# PandaSat_Payload.net
KiCad netlist of a schematic drawn in EAGLE
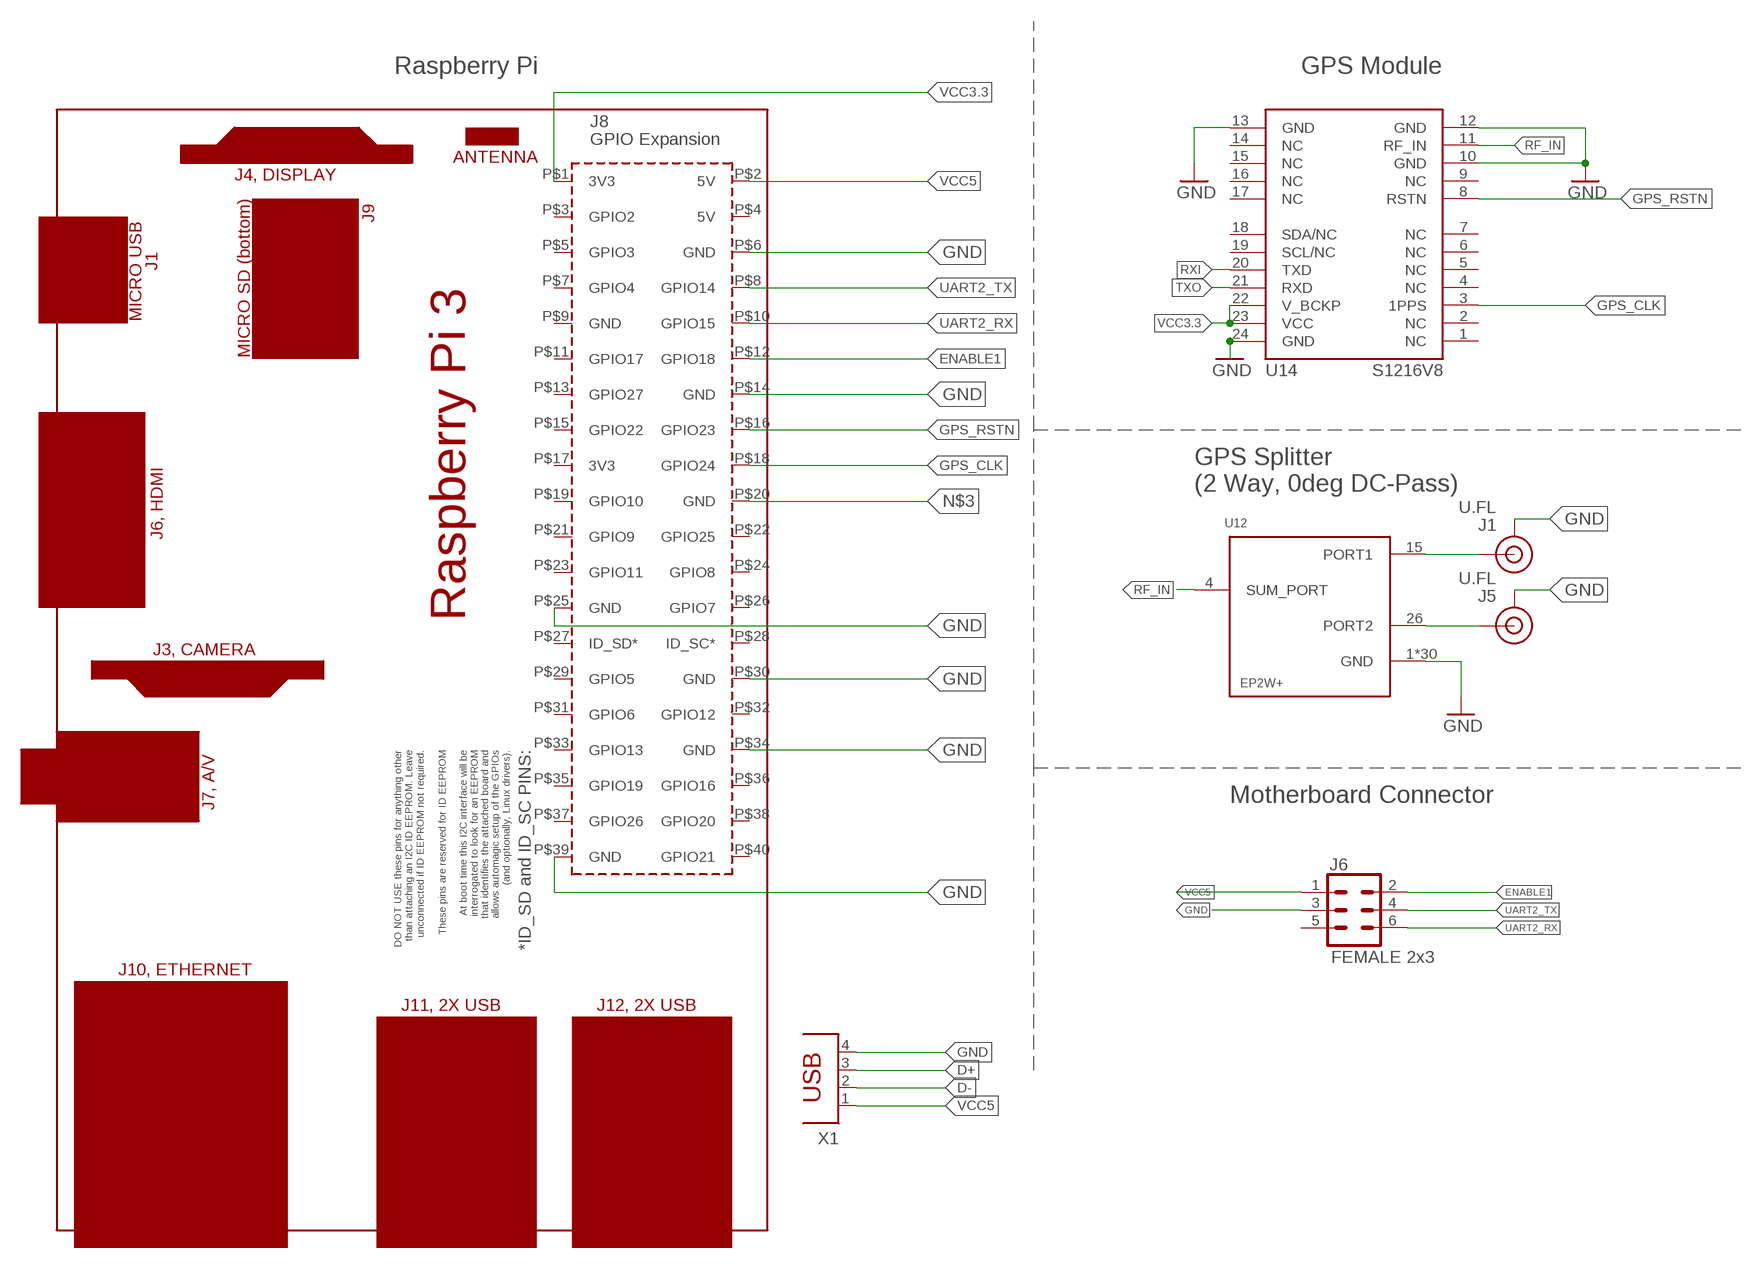
[diagram p0: schematic, sheet 1]
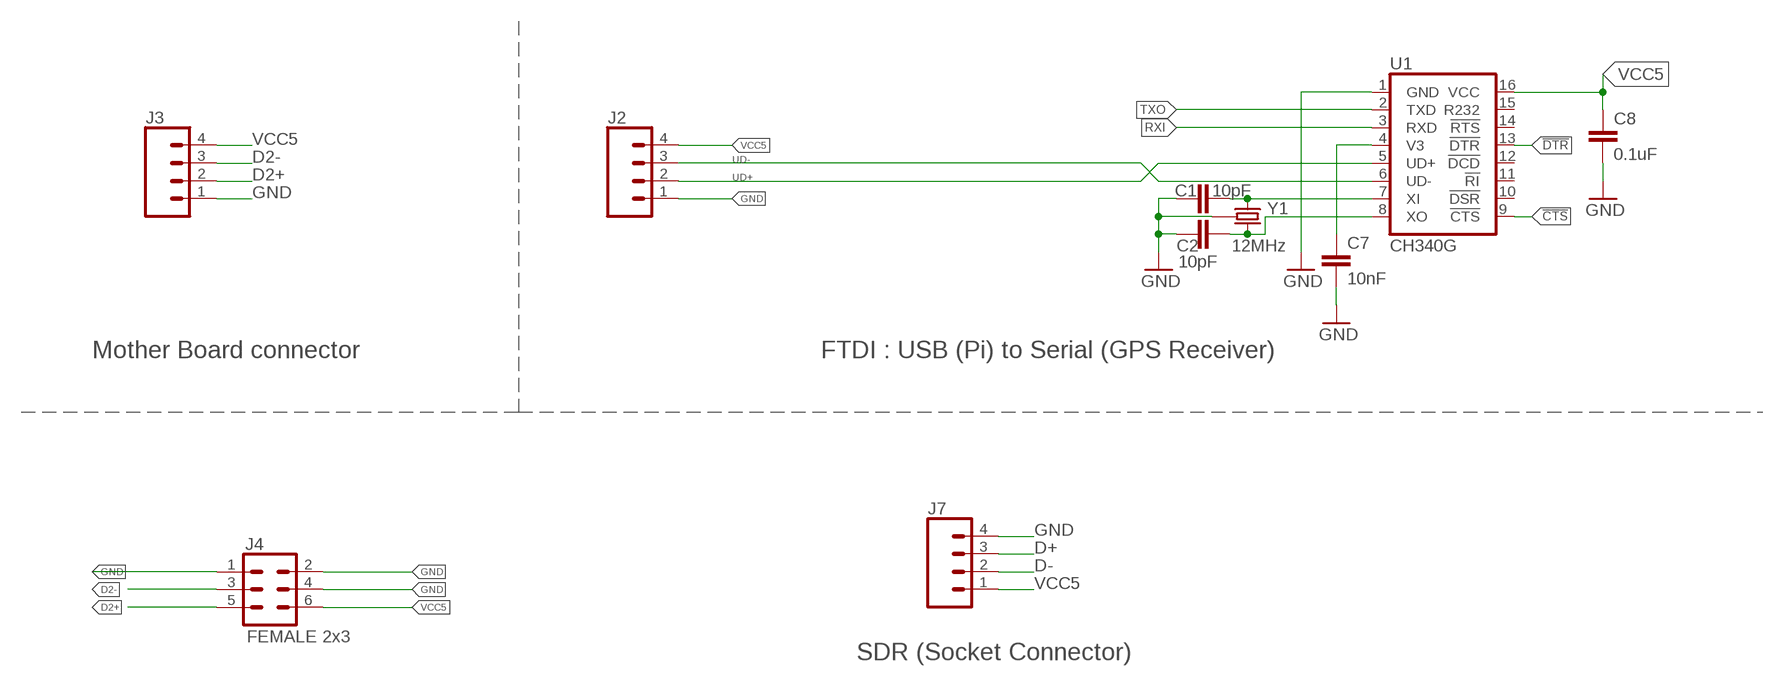
[diagram p1: schematic, sheet 2]

(export (version "E")
  (design (tool "Eeschema 10.0.6"))
  (components
    (comp (ref "C1")
      (value "10pF")
      (footprint "eagle-import:0603-CAP")
      (libsource (lib "eagle-import") (part "10PF-50V-5%(0603)"))
    )
    (comp (ref "C2")
      (value "10pF")
      (footprint "eagle-import:0603-CAP")
      (libsource (lib "eagle-import") (part "10PF-50V-5%(0603)"))
    )
    (comp (ref "C7")
      (value "10nF")
      (footprint "eagle-import:0603-CAP")
      (libsource (lib "eagle-import") (part "10NF/10000PF-50V-10%(0603)"))
    )
    (comp (ref "C8")
      (value "0.1uF")
      (footprint "eagle-import:0603-CAP")
      (libsource (lib "eagle-import") (part "0.1UF-25V(+80/-20%)(0603)"))
    )
    (comp (ref "J2")
      (value "CONN_04")
      (footprint "eagle-import:1X04")
      (libsource (lib "eagle-import") (part "CONN_04"))
    )
    (comp (ref "J3")
      (value "CONN_04")
      (footprint "eagle-import:1X04")
      (libsource (lib "eagle-import") (part "CONN_04"))
    )
    (comp (ref "J4")
      (value "FEMALE 2x3")
      (footprint "eagle-import:2X3")
      (libsource (lib "eagle-import") (part "CONN_03X2FEMALE"))
    )
    (comp (ref "J7")
      (value "CONN_04")
      (footprint "eagle-import:1X04")
      (libsource (lib "eagle-import") (part "CONN_04"))
    )
    (comp (ref "U1")
      (value "CH340G")
      (footprint "eagle-import:SO016")
      (libsource (lib "eagle-import") (part "CH340GSMD"))
    )
    (comp (ref "Y1")
      (value "12MHz")
      (footprint "eagle-import:CRYSTAL-SMD-3.2X2.5")
      (libsource (lib "eagle-import") (part "CRYSTAL-GROUNDED3.2X2.5"))
    )
    (comp (ref "J1")
      (value "U.FL")
      (footprint "eagle-import:U.FL")
      (libsource (lib "eagle-import") (part "U.FL2PIN"))
    )
    (comp (ref "J5")
      (value "U.FL")
      (footprint "eagle-import:U.FL")
      (libsource (lib "eagle-import") (part "U.FL2PIN"))
    )
    (comp (ref "J6")
      (value "FEMALE 2x3")
      (footprint "eagle-import:2X3")
      (libsource (lib "eagle-import") (part "CONN_03X2FEMALE"))
    )
    (comp (ref "PCB1")
      (value "RPI3RPI3")
      (footprint "eagle-import:RPI3")
      (libsource (lib "eagle-import") (part "RPI3RPI3"))
    )
    (comp (ref "U12")
      (value "EP2W+")
      (footprint "eagle-import:QFN32-5X5MM")
      (libsource (lib "eagle-import") (part "EP2W+"))
    )
    (comp (ref "U14")
      (value "S1216V8")
      (footprint "eagle-import:S1216_24PIN_PACKAGE")
      (libsource (lib "eagle-import") (part "S1216V8"))
    )
    (comp (ref "X1")
      (value "PN87520")
      (footprint "eagle-import:PN87520")
      (libsource (lib "eagle-import") (part "PN87520"))
    )
  )
  (nets
    (net (code "1") (name "D+") (class "Default")
      (node (ref "J7") (pin "3") (pinfunction "3_3") (pintype "passive"))
      (node (ref "X1") (pin "3") (pinfunction "3_3") (pintype "passive"))
    )
    (net (code "2") (name "D-") (class "Default")
      (node (ref "J7") (pin "2") (pinfunction "2_2") (pintype "passive"))
      (node (ref "X1") (pin "2") (pinfunction "2_2") (pintype "passive"))
    )
    (net (code "3") (name "D2+") (class "Default")
      (node (ref "J3") (pin "2") (pinfunction "2_2") (pintype "passive"))
      (node (ref "J4") (pin "5") (pinfunction "5_5") (pintype "bidirectional"))
    )
    (net (code "4") (name "D2-") (class "Default")
      (node (ref "J3") (pin "3") (pinfunction "3_3") (pintype "passive"))
      (node (ref "J4") (pin "3") (pinfunction "3_3") (pintype "bidirectional"))
    )
    (net (code "5") (name "ENABLE1") (class "Default")
      (node (ref "J6") (pin "2") (pinfunction "2_2") (pintype "bidirectional"))
      (node (ref "PCB1") (pin "P$12") (pinfunction "GPIO18_P$12") (pintype "bidirectional"))
    )
    (net (code "6") (name "GND") (class "Default")
      (node (ref "C1") (pin "1") (pinfunction "1_1") (pintype "passive"))
      (node (ref "C2") (pin "1") (pinfunction "1_1") (pintype "passive"))
      (node (ref "C7") (pin "2") (pinfunction "2_2") (pintype "passive"))
      (node (ref "C8") (pin "2") (pinfunction "2_2") (pintype "passive"))
      (node (ref "J1") (pin "1") (pinfunction "GND_1") (pintype "bidirectional"))
      (node (ref "J1") (pin "2") (pinfunction "GND_2") (pintype "bidirectional"))
      (node (ref "J2") (pin "1") (pinfunction "1_1") (pintype "passive"))
      (node (ref "J3") (pin "1") (pinfunction "1_1") (pintype "passive"))
      (node (ref "J4") (pin "1") (pinfunction "1_1") (pintype "bidirectional"))
      (node (ref "J4") (pin "2") (pinfunction "2_2") (pintype "bidirectional"))
      (node (ref "J4") (pin "4") (pinfunction "4_4") (pintype "bidirectional"))
      (node (ref "J5") (pin "1") (pinfunction "GND_1") (pintype "bidirectional"))
      (node (ref "J5") (pin "2") (pinfunction "GND_2") (pintype "bidirectional"))
      (node (ref "J6") (pin "3") (pinfunction "3_3") (pintype "bidirectional"))
      (node (ref "J7") (pin "4") (pinfunction "4_4") (pintype "passive"))
      (node (ref "PCB1") (pin "P$14") (pinfunction "GND_P$14") (pintype "bidirectional"))
      (node (ref "PCB1") (pin "P$25") (pinfunction "GND_P$25") (pintype "bidirectional"))
      (node (ref "PCB1") (pin "P$30") (pinfunction "GND_P$30") (pintype "bidirectional"))
      (node (ref "PCB1") (pin "P$34") (pinfunction "GND_P$34") (pintype "bidirectional"))
      (node (ref "PCB1") (pin "P$39") (pinfunction "GND_P$39") (pintype "bidirectional"))
      (node (ref "PCB1") (pin "P$6") (pinfunction "GND_P$6") (pintype "bidirectional"))
      (node (ref "U1") (pin "1") (pinfunction "GND_1") (pintype "bidirectional"))
      (node (ref "U12") (pin "1") (pinfunction "GND_1") (pintype "bidirectional"))
      (node (ref "U12") (pin "10") (pinfunction "GND_10") (pintype "bidirectional"))
      (node (ref "U12") (pin "11") (pinfunction "GND_11") (pintype "bidirectional"))
      (node (ref "U12") (pin "12") (pinfunction "GND_12") (pintype "bidirectional"))
      (node (ref "U12") (pin "13") (pinfunction "GND_13") (pintype "bidirectional"))
      (node (ref "U12") (pin "14") (pinfunction "GND_14") (pintype "bidirectional"))
      (node (ref "U12") (pin "16") (pinfunction "GND_16") (pintype "bidirectional"))
      (node (ref "U12") (pin "17") (pinfunction "GND_17") (pintype "bidirectional"))
      (node (ref "U12") (pin "18") (pinfunction "GND_18") (pintype "bidirectional"))
      (node (ref "U12") (pin "19") (pinfunction "GND_19") (pintype "bidirectional"))
      (node (ref "U12") (pin "2") (pinfunction "GND_2") (pintype "bidirectional"))
      (node (ref "U12") (pin "20") (pinfunction "GND_20") (pintype "bidirectional"))
      (node (ref "U12") (pin "21") (pinfunction "GND_21") (pintype "bidirectional"))
      (node (ref "U12") (pin "22") (pinfunction "GND_22") (pintype "bidirectional"))
      (node (ref "U12") (pin "23") (pinfunction "GND_23") (pintype "bidirectional"))
      (node (ref "U12") (pin "24") (pinfunction "GND_24") (pintype "bidirectional"))
      (node (ref "U12") (pin "25") (pinfunction "GND_25") (pintype "bidirectional"))
      (node (ref "U12") (pin "27") (pinfunction "GND_27") (pintype "bidirectional"))
      (node (ref "U12") (pin "28") (pinfunction "GND_28") (pintype "bidirectional"))
      (node (ref "U12") (pin "29") (pinfunction "GND_29") (pintype "bidirectional"))
      (node (ref "U12") (pin "3") (pinfunction "GND_3") (pintype "bidirectional"))
      (node (ref "U12") (pin "30") (pinfunction "GND_30") (pintype "bidirectional"))
      (node (ref "U12") (pin "31") (pinfunction "GND_31") (pintype "bidirectional"))
      (node (ref "U12") (pin "32") (pinfunction "GND_32") (pintype "bidirectional"))
      (node (ref "U12") (pin "5") (pinfunction "GND_5") (pintype "bidirectional"))
      (node (ref "U12") (pin "6") (pinfunction "GND_6") (pintype "bidirectional"))
      (node (ref "U12") (pin "7") (pinfunction "GND_7") (pintype "bidirectional"))
      (node (ref "U12") (pin "8") (pinfunction "GND_8") (pintype "bidirectional"))
      (node (ref "U12") (pin "9") (pinfunction "GND_9") (pintype "bidirectional"))
      (node (ref "U12") (pin "EP") (pinfunction "GND_EP") (pintype "bidirectional"))
      (node (ref "U14") (pin "10") (pinfunction "GND_10") (pintype "bidirectional"))
      (node (ref "U14") (pin "12") (pinfunction "GND_12") (pintype "bidirectional"))
      (node (ref "U14") (pin "13") (pinfunction "GND_13") (pintype "bidirectional"))
      (node (ref "U14") (pin "24") (pinfunction "GND_24") (pintype "bidirectional"))
      (node (ref "X1") (pin "4") (pinfunction "4_4") (pintype "passive"))
      (node (ref "Y1") (pin "2") (pinfunction "GND_2") (pintype "passive"))
      (node (ref "Y1") (pin "4") (pinfunction "GND_4") (pintype "passive"))
    )
    (net (code "7") (name "GPS_CLK") (class "Default")
      (node (ref "PCB1") (pin "P$18") (pinfunction "GPIO24_P$18") (pintype "bidirectional"))
      (node (ref "U14") (pin "3") (pinfunction "1PPS_3") (pintype "bidirectional"))
    )
    (net (code "8") (name "GPS_RSTN") (class "Default")
      (node (ref "PCB1") (pin "P$16") (pinfunction "GPIO23_P$16") (pintype "bidirectional"))
      (node (ref "U14") (pin "8") (pinfunction "RSTN_8") (pintype "bidirectional"))
    )
    (net (code "9") (name "N$3") (class "Default")
      (node (ref "PCB1") (pin "P$20") (pinfunction "GND_P$20") (pintype "bidirectional"))
    )
    (net (code "10") (name "Net-(J1-SIGNAL)") (class "Default")
      (node (ref "J1") (pin "FEED") (pinfunction "SIGNAL_FEED") (pintype "bidirectional"))
      (node (ref "U12") (pin "15") (pinfunction "PORT1_15") (pintype "bidirectional"))
    )
    (net (code "11") (name "Net-(J5-SIGNAL)") (class "Default")
      (node (ref "J5") (pin "FEED") (pinfunction "SIGNAL_FEED") (pintype "bidirectional"))
      (node (ref "U12") (pin "26") (pinfunction "PORT2_26") (pintype "bidirectional"))
    )
    (net (code "12") (name "Net-(U1-V3)") (class "Default")
      (node (ref "C7") (pin "1") (pinfunction "1_1") (pintype "passive"))
      (node (ref "U1") (pin "4") (pinfunction "V3_4") (pintype "bidirectional"))
    )
    (net (code "13") (name "Net-(U1-XI)") (class "Default")
      (node (ref "C1") (pin "2") (pinfunction "2_2") (pintype "passive"))
      (node (ref "U1") (pin "7") (pinfunction "XI_7") (pintype "bidirectional"))
      (node (ref "Y1") (pin "1") (pinfunction "1_1") (pintype "passive"))
    )
    (net (code "14") (name "Net-(U1-XO)") (class "Default")
      (node (ref "C2") (pin "2") (pinfunction "2_2") (pintype "passive"))
      (node (ref "U1") (pin "8") (pinfunction "XO_8") (pintype "bidirectional"))
      (node (ref "Y1") (pin "3") (pinfunction "2_3") (pintype "passive"))
    )
    (net (code "15") (name "RF_IN") (class "Default")
      (node (ref "U12") (pin "4") (pinfunction "SUM_PORT_4") (pintype "bidirectional"))
      (node (ref "U14") (pin "11") (pinfunction "RF_IN_11") (pintype "bidirectional"))
    )
    (net (code "16") (name "RXI") (class "Default")
      (node (ref "U1") (pin "3") (pinfunction "RXD_3") (pintype "bidirectional"))
      (node (ref "U14") (pin "20") (pinfunction "TXD_20") (pintype "bidirectional"))
    )
    (net (code "17") (name "TXO") (class "Default")
      (node (ref "U1") (pin "2") (pinfunction "TXD_2") (pintype "bidirectional"))
      (node (ref "U14") (pin "21") (pinfunction "RXD_21") (pintype "bidirectional"))
    )
    (net (code "18") (name "UART2_RX") (class "Default")
      (node (ref "J6") (pin "6") (pinfunction "6_6") (pintype "bidirectional"))
      (node (ref "PCB1") (pin "P$10") (pinfunction "GPIO15_P$10") (pintype "bidirectional"))
    )
    (net (code "19") (name "UART2_TX") (class "Default")
      (node (ref "J6") (pin "4") (pinfunction "4_4") (pintype "bidirectional"))
      (node (ref "PCB1") (pin "P$8") (pinfunction "GPIO14_P$8") (pintype "bidirectional"))
    )
    (net (code "20") (name "UD+") (class "Default")
      (node (ref "J2") (pin "2") (pinfunction "2_2") (pintype "passive"))
      (node (ref "U1") (pin "5") (pinfunction "UD+_5") (pintype "bidirectional"))
    )
    (net (code "21") (name "UD-") (class "Default")
      (node (ref "J2") (pin "3") (pinfunction "3_3") (pintype "passive"))
      (node (ref "U1") (pin "6") (pinfunction "UD-_6") (pintype "bidirectional"))
    )
    (net (code "22") (name "VCC3.3") (class "Default")
      (node (ref "PCB1") (pin "P$1") (pinfunction "3V3_P$1") (pintype "bidirectional"))
      (node (ref "U14") (pin "22") (pinfunction "V_BCKP_22") (pintype "bidirectional"))
      (node (ref "U14") (pin "23") (pinfunction "VCC_23") (pintype "bidirectional"))
    )
    (net (code "23") (name "VCC5") (class "Default")
      (node (ref "C8") (pin "1") (pinfunction "1_1") (pintype "passive"))
      (node (ref "J2") (pin "4") (pinfunction "4_4") (pintype "passive"))
      (node (ref "J3") (pin "4") (pinfunction "4_4") (pintype "passive"))
      (node (ref "J4") (pin "6") (pinfunction "6_6") (pintype "bidirectional"))
      (node (ref "J6") (pin "1") (pinfunction "1_1") (pintype "bidirectional"))
      (node (ref "J7") (pin "1") (pinfunction "1_1") (pintype "passive"))
      (node (ref "PCB1") (pin "P$2") (pinfunction "5V_P$2") (pintype "bidirectional"))
      (node (ref "U1") (pin "16") (pinfunction "VCC_16") (pintype "bidirectional"))
      (node (ref "X1") (pin "1") (pinfunction "1_1") (pintype "passive"))
    )
    (net (code "24") (name "unconnected-(J6-Pad5)") (class "Default")
      (node (ref "J6") (pin "5") (pinfunction "5_5") (pintype "bidirectional"))
    )
    (net (code "25") (name "unconnected-(PCB1-3V3-PadP$17)") (class "Default")
      (node (ref "PCB1") (pin "P$17") (pinfunction "3V3_P$17") (pintype "bidirectional"))
    )
    (net (code "26") (name "unconnected-(PCB1-5V-PadP$4)") (class "Default")
      (node (ref "PCB1") (pin "P$4") (pinfunction "5V_P$4") (pintype "bidirectional"))
    )
    (net (code "27") (name "unconnected-(PCB1-GND-PadP$9)") (class "Default")
      (node (ref "PCB1") (pin "P$9") (pinfunction "GND_P$9") (pintype "bidirectional"))
    )
    (net (code "28") (name "unconnected-(PCB1-GPIO2-PadP$3)") (class "Default")
      (node (ref "PCB1") (pin "P$3") (pinfunction "GPIO2_P$3") (pintype "bidirectional"))
    )
    (net (code "29") (name "unconnected-(PCB1-GPIO3-PadP$5)") (class "Default")
      (node (ref "PCB1") (pin "P$5") (pinfunction "GPIO3_P$5") (pintype "bidirectional"))
    )
    (net (code "30") (name "unconnected-(PCB1-GPIO4-PadP$7)") (class "Default")
      (node (ref "PCB1") (pin "P$7") (pinfunction "GPIO4_P$7") (pintype "bidirectional"))
    )
    (net (code "31") (name "unconnected-(PCB1-GPIO5-PadP$29)") (class "Default")
      (node (ref "PCB1") (pin "P$29") (pinfunction "GPIO5_P$29") (pintype "bidirectional"))
    )
    (net (code "32") (name "unconnected-(PCB1-GPIO6-PadP$31)") (class "Default")
      (node (ref "PCB1") (pin "P$31") (pinfunction "GPIO6_P$31") (pintype "bidirectional"))
    )
    (net (code "33") (name "unconnected-(PCB1-GPIO7-PadP$26)") (class "Default")
      (node (ref "PCB1") (pin "P$26") (pinfunction "GPIO7_P$26") (pintype "bidirectional"))
    )
    (net (code "34") (name "unconnected-(PCB1-GPIO8-PadP$24)") (class "Default")
      (node (ref "PCB1") (pin "P$24") (pinfunction "GPIO8_P$24") (pintype "bidirectional"))
    )
    (net (code "35") (name "unconnected-(PCB1-GPIO9-PadP$21)") (class "Default")
      (node (ref "PCB1") (pin "P$21") (pinfunction "GPIO9_P$21") (pintype "bidirectional"))
    )
    (net (code "36") (name "unconnected-(PCB1-GPIO10-PadP$19)") (class "Default")
      (node (ref "PCB1") (pin "P$19") (pinfunction "GPIO10_P$19") (pintype "bidirectional"))
    )
    (net (code "37") (name "unconnected-(PCB1-GPIO11-PadP$23)") (class "Default")
      (node (ref "PCB1") (pin "P$23") (pinfunction "GPIO11_P$23") (pintype "bidirectional"))
    )
    (net (code "38") (name "unconnected-(PCB1-GPIO12-PadP$32)") (class "Default")
      (node (ref "PCB1") (pin "P$32") (pinfunction "GPIO12_P$32") (pintype "bidirectional"))
    )
    (net (code "39") (name "unconnected-(PCB1-GPIO13-PadP$33)") (class "Default")
      (node (ref "PCB1") (pin "P$33") (pinfunction "GPIO13_P$33") (pintype "bidirectional"))
    )
    (net (code "40") (name "unconnected-(PCB1-GPIO16-PadP$36)") (class "Default")
      (node (ref "PCB1") (pin "P$36") (pinfunction "GPIO16_P$36") (pintype "bidirectional"))
    )
    (net (code "41") (name "unconnected-(PCB1-GPIO17-PadP$11)") (class "Default")
      (node (ref "PCB1") (pin "P$11") (pinfunction "GPIO17_P$11") (pintype "bidirectional"))
    )
    (net (code "42") (name "unconnected-(PCB1-GPIO19-PadP$35)") (class "Default")
      (node (ref "PCB1") (pin "P$35") (pinfunction "GPIO19_P$35") (pintype "bidirectional"))
    )
    (net (code "43") (name "unconnected-(PCB1-GPIO20-PadP$38)") (class "Default")
      (node (ref "PCB1") (pin "P$38") (pinfunction "GPIO20_P$38") (pintype "bidirectional"))
    )
    (net (code "44") (name "unconnected-(PCB1-GPIO21-PadP$40)") (class "Default")
      (node (ref "PCB1") (pin "P$40") (pinfunction "GPIO21_P$40") (pintype "bidirectional"))
    )
    (net (code "45") (name "unconnected-(PCB1-GPIO22-PadP$15)") (class "Default")
      (node (ref "PCB1") (pin "P$15") (pinfunction "GPIO22_P$15") (pintype "bidirectional"))
    )
    (net (code "46") (name "unconnected-(PCB1-GPIO25-PadP$22)") (class "Default")
      (node (ref "PCB1") (pin "P$22") (pinfunction "GPIO25_P$22") (pintype "bidirectional"))
    )
    (net (code "47") (name "unconnected-(PCB1-GPIO26-PadP$37)") (class "Default")
      (node (ref "PCB1") (pin "P$37") (pinfunction "GPIO26_P$37") (pintype "bidirectional"))
    )
    (net (code "48") (name "unconnected-(PCB1-GPIO27-PadP$13)") (class "Default")
      (node (ref "PCB1") (pin "P$13") (pinfunction "GPIO27_P$13") (pintype "bidirectional"))
    )
    (net (code "49") (name "unconnected-(PCB1-ID_SC*-PadP$28)") (class "Default")
      (node (ref "PCB1") (pin "P$28") (pinfunction "ID_SC*_P$28") (pintype "bidirectional"))
    )
    (net (code "50") (name "unconnected-(PCB1-ID_SD*-PadP$27)") (class "Default")
      (node (ref "PCB1") (pin "P$27") (pinfunction "ID_SD*_P$27") (pintype "bidirectional"))
    )
    (net (code "51") (name "unconnected-(U1-R232-Pad15)") (class "Default")
      (node (ref "U1") (pin "15") (pinfunction "R232_15") (pintype "bidirectional"))
    )
    (net (code "52") (name "unconnected-(U1-~{DCD}-Pad12)") (class "Default")
      (node (ref "U1") (pin "12") (pinfunction "~{DCD}_12") (pintype "bidirectional"))
    )
    (net (code "53") (name "unconnected-(U1-~{DSR}-Pad10)") (class "Default")
      (node (ref "U1") (pin "10") (pinfunction "~{DSR}_10") (pintype "bidirectional"))
    )
    (net (code "54") (name "unconnected-(U1-~{RI}-Pad11)") (class "Default")
      (node (ref "U1") (pin "11") (pinfunction "~{RI}_11") (pintype "bidirectional"))
    )
    (net (code "55") (name "unconnected-(U1-~{RTS}-Pad14)") (class "Default")
      (node (ref "U1") (pin "14") (pinfunction "~{RTS}_14") (pintype "bidirectional"))
    )
    (net (code "56") (name "unconnected-(U14-NC-Pad1)") (class "Default")
      (node (ref "U14") (pin "1") (pinfunction "NC_1") (pintype "bidirectional"))
    )
    (net (code "57") (name "unconnected-(U14-NC-Pad2)") (class "Default")
      (node (ref "U14") (pin "2") (pinfunction "NC_2") (pintype "bidirectional"))
    )
    (net (code "58") (name "unconnected-(U14-NC-Pad4)") (class "Default")
      (node (ref "U14") (pin "4") (pinfunction "NC_4") (pintype "bidirectional"))
    )
    (net (code "59") (name "unconnected-(U14-NC-Pad5)") (class "Default")
      (node (ref "U14") (pin "5") (pinfunction "NC_5") (pintype "bidirectional"))
    )
    (net (code "60") (name "unconnected-(U14-NC-Pad6)") (class "Default")
      (node (ref "U14") (pin "6") (pinfunction "NC_6") (pintype "bidirectional"))
    )
    (net (code "61") (name "unconnected-(U14-NC-Pad7)") (class "Default")
      (node (ref "U14") (pin "7") (pinfunction "NC_7") (pintype "bidirectional"))
    )
    (net (code "62") (name "unconnected-(U14-NC-Pad9)") (class "Default")
      (node (ref "U14") (pin "9") (pinfunction "NC_9") (pintype "bidirectional"))
    )
    (net (code "63") (name "unconnected-(U14-NC-Pad14)") (class "Default")
      (node (ref "U14") (pin "14") (pinfunction "NC_14") (pintype "bidirectional"))
    )
    (net (code "64") (name "unconnected-(U14-NC-Pad15)") (class "Default")
      (node (ref "U14") (pin "15") (pinfunction "NC_15") (pintype "bidirectional"))
    )
    (net (code "65") (name "unconnected-(U14-NC-Pad16)") (class "Default")
      (node (ref "U14") (pin "16") (pinfunction "NC_16") (pintype "bidirectional"))
    )
    (net (code "66") (name "unconnected-(U14-NC-Pad17)") (class "Default")
      (node (ref "U14") (pin "17") (pinfunction "NC_17") (pintype "bidirectional"))
    )
    (net (code "67") (name "unconnected-(U14-SCL{slash}NC-Pad19)") (class "Default")
      (node (ref "U14") (pin "19") (pinfunction "SCL/NC_19") (pintype "bidirectional"))
    )
    (net (code "68") (name "unconnected-(U14-SDA{slash}NC-Pad18)") (class "Default")
      (node (ref "U14") (pin "18") (pinfunction "SDA/NC_18") (pintype "bidirectional"))
    )
    (net (code "69") (name "~{CTS}") (class "Default")
      (node (ref "U1") (pin "9") (pinfunction "~{CTS}_9") (pintype "bidirectional"))
    )
    (net (code "70") (name "~{DTR}") (class "Default")
      (node (ref "U1") (pin "13") (pinfunction "~{DTR}_13") (pintype "bidirectional"))
    )
  )
)
